# midicontrol_v5.net
KiCad netlist of a schematic drawn in EAGLE
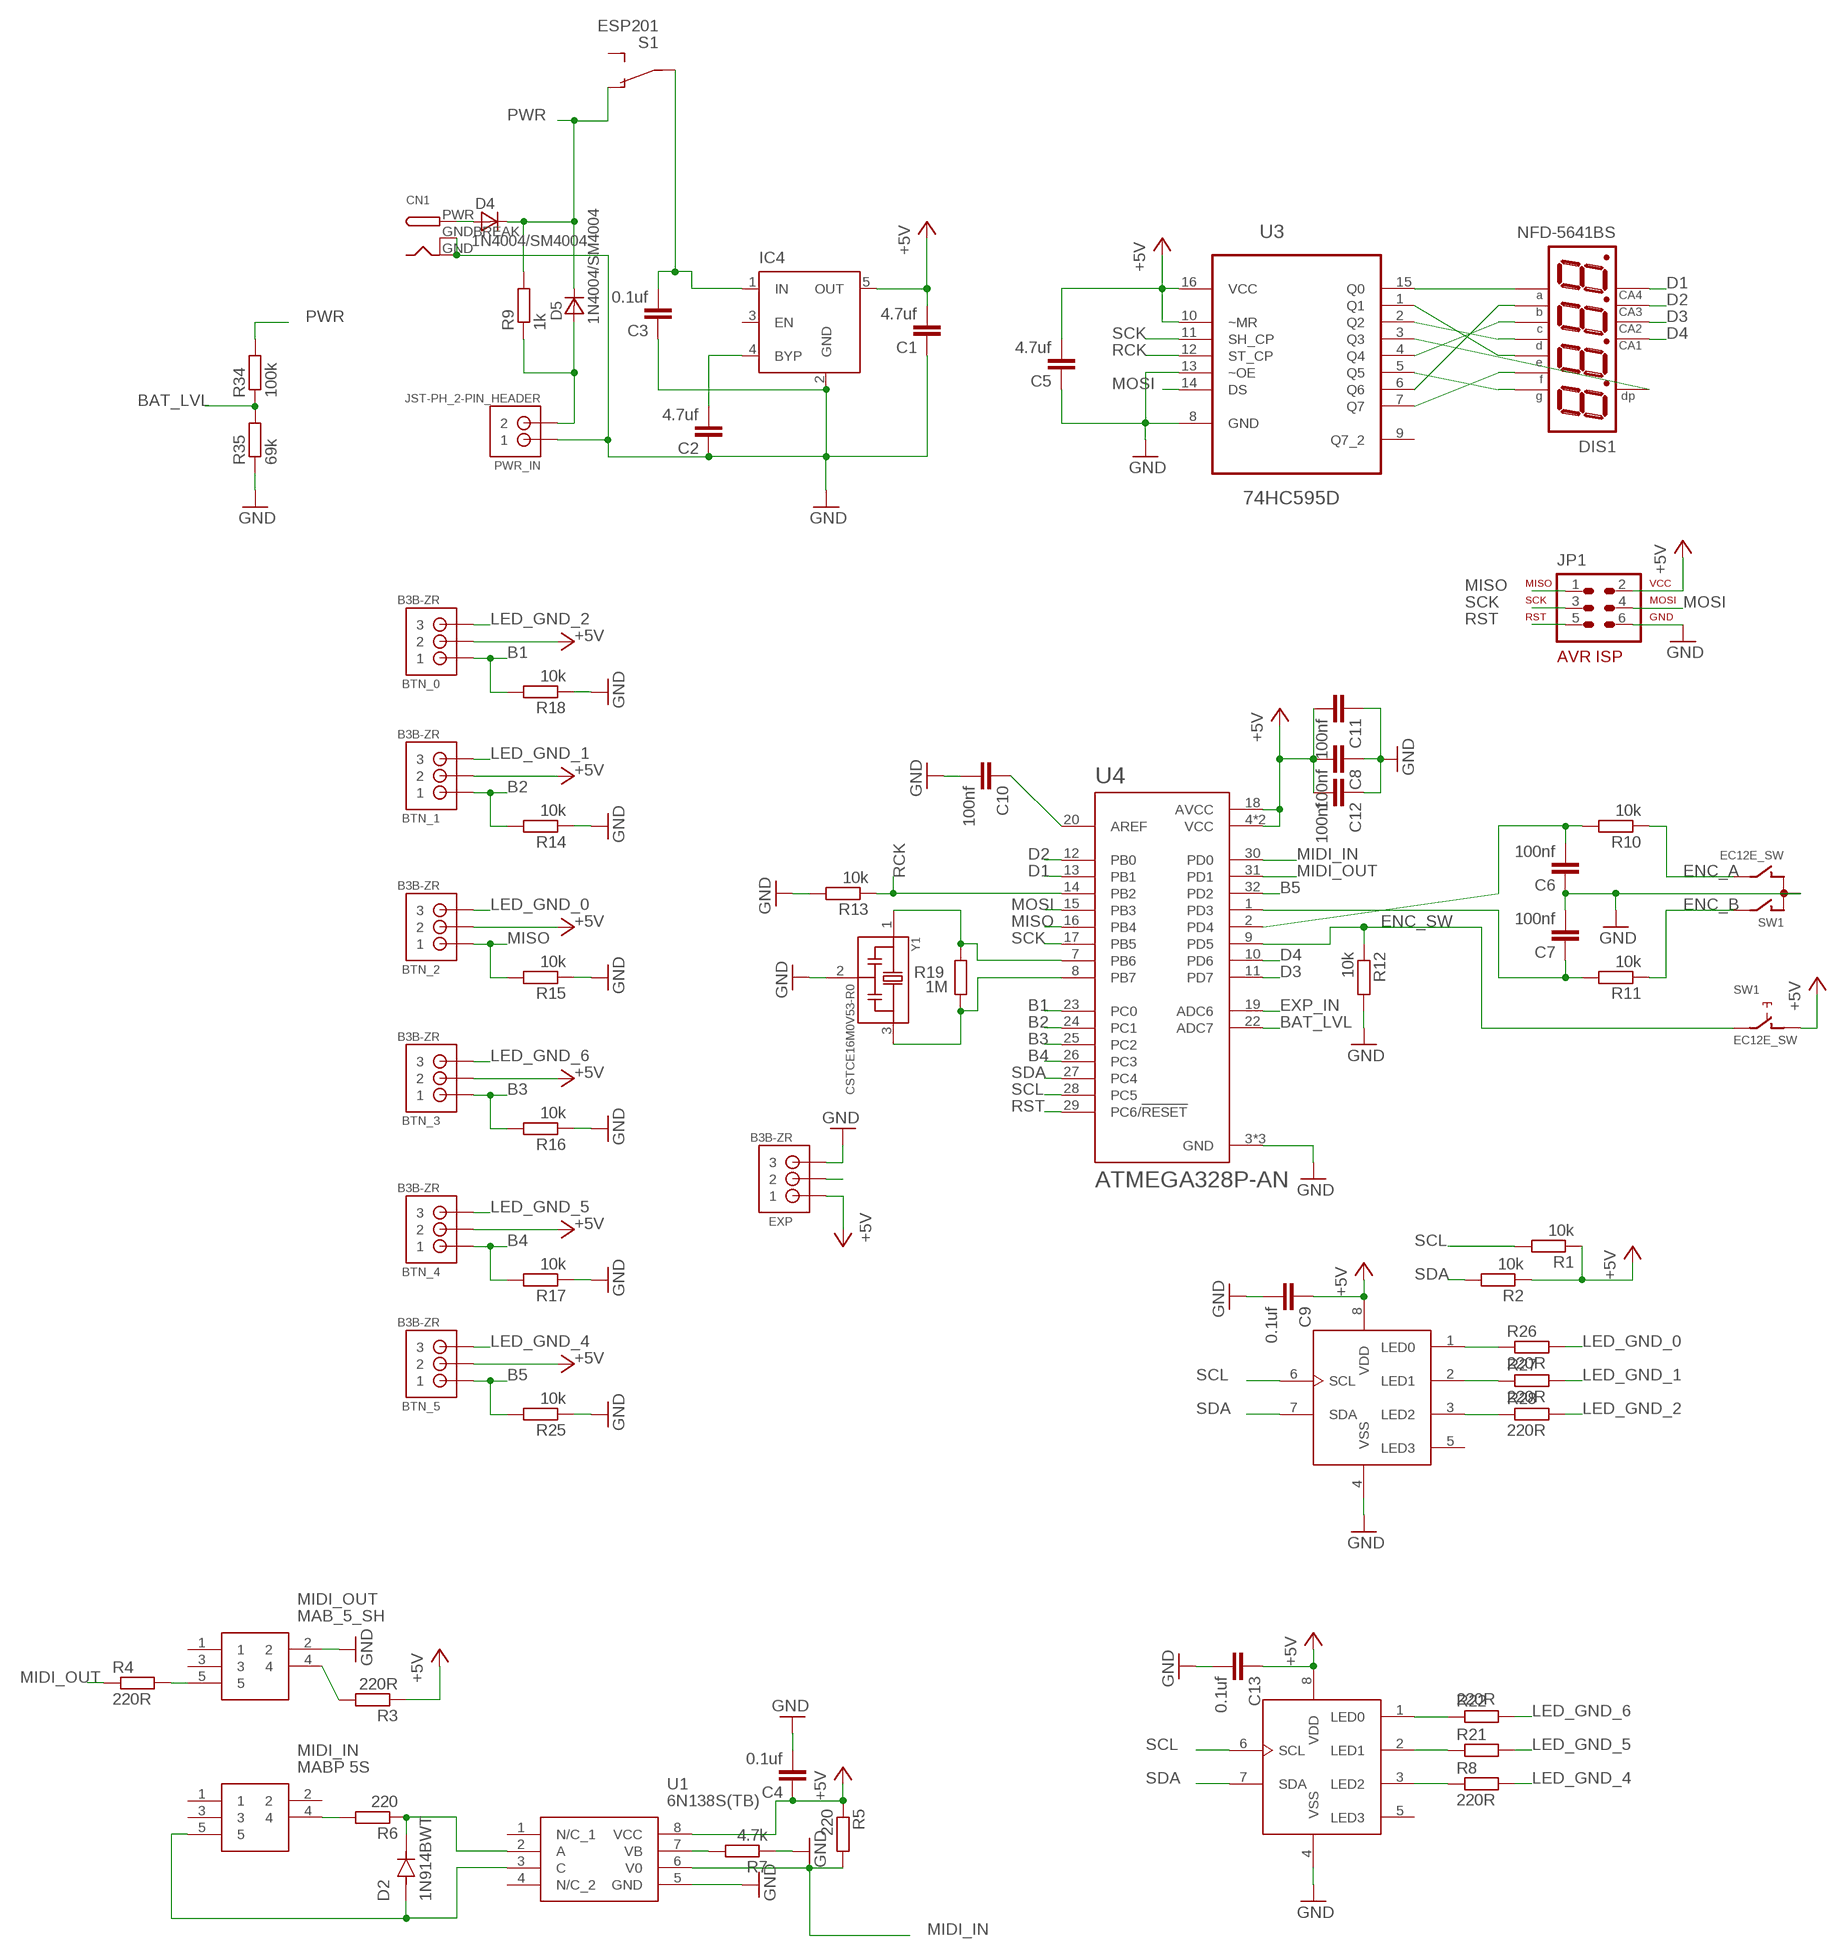
[diagram p0: schematic, sheet 1]

(export (version "E")
  (design (tool "Eeschema 10.0.6"))
  (components
    (comp (ref "BTN_0")
      (value "B3B-ZR")
      (footprint "eagle-import:B3B-ZR")
      (libsource (lib "eagle-import") (part "B3B-ZR"))
    )
    (comp (ref "BTN_1")
      (value "B3B-ZR")
      (footprint "eagle-import:B3B-ZR")
      (libsource (lib "eagle-import") (part "B3B-ZR"))
    )
    (comp (ref "BTN_2")
      (value "B3B-ZR")
      (footprint "eagle-import:B3B-ZR")
      (libsource (lib "eagle-import") (part "B3B-ZR"))
    )
    (comp (ref "BTN_3")
      (value "B3B-ZR")
      (footprint "eagle-import:B3B-ZR")
      (libsource (lib "eagle-import") (part "B3B-ZR"))
    )
    (comp (ref "BTN_4")
      (value "B3B-ZR")
      (footprint "eagle-import:B3B-ZR")
      (libsource (lib "eagle-import") (part "B3B-ZR"))
    )
    (comp (ref "BTN_5")
      (value "B3B-ZR")
      (footprint "eagle-import:B3B-ZR")
      (libsource (lib "eagle-import") (part "B3B-ZR"))
    )
    (comp (ref "C1")
      (value "4.7uf")
      (footprint "eagle-import:C1206")
      (libsource (lib "eagle-import") (part "C-EUC1206"))
    )
    (comp (ref "C2")
      (value "4.7uf")
      (footprint "eagle-import:C1206")
      (libsource (lib "eagle-import") (part "C-EUC1206"))
    )
    (comp (ref "C3")
      (value "0.1uf")
      (footprint "eagle-import:C1206")
      (libsource (lib "eagle-import") (part "C-EUC1206"))
    )
    (comp (ref "C4")
      (value "0.1uf")
      (footprint "eagle-import:C0603")
      (libsource (lib "eagle-import") (part "C-EUC0603"))
    )
    (comp (ref "C5")
      (value "4.7uf")
      (footprint "eagle-import:C0603")
      (libsource (lib "eagle-import") (part "C-EUC0603"))
    )
    (comp (ref "C6")
      (value "100nf")
      (footprint "eagle-import:C0603")
      (libsource (lib "eagle-import") (part "C-EUC0603"))
    )
    (comp (ref "C7")
      (value "100nf")
      (footprint "eagle-import:C0603")
      (libsource (lib "eagle-import") (part "C-EUC0603"))
    )
    (comp (ref "C8")
      (value "100nf")
      (footprint "eagle-import:C1206")
      (libsource (lib "eagle-import") (part "C-EUC1206"))
    )
    (comp (ref "C9")
      (value "0.1uf")
      (footprint "eagle-import:C0603")
      (libsource (lib "eagle-import") (part "C-EUC0603"))
    )
    (comp (ref "C10")
      (value "100nf")
      (footprint "eagle-import:C0603")
      (libsource (lib "eagle-import") (part "C-EUC0603"))
    )
    (comp (ref "C11")
      (value "100nf")
      (footprint "eagle-import:C0603")
      (libsource (lib "eagle-import") (part "C-EUC0603"))
    )
    (comp (ref "C12")
      (value "100nf")
      (footprint "eagle-import:C0603")
      (libsource (lib "eagle-import") (part "C-EUC0603"))
    )
    (comp (ref "C13")
      (value "0.1uf")
      (footprint "eagle-import:C0603")
      (libsource (lib "eagle-import") (part "C-EUC0603"))
    )
    (comp (ref "CN1")
      (value "DCBARRELPTH")
      (footprint "eagle-import:DCJACK_2MM_PTH")
      (libsource (lib "eagle-import") (part "DCBARRELPTH"))
    )
    (comp (ref "D2")
      (value "1N914BWT")
      (footprint "eagle-import:SODFL1608X70N")
      (fields (field (name "MF") "ON Semiconductor"))
      (libsource (lib "eagle-import") (part "1N914BWT"))
    )
    (comp (ref "D4")
      (value "1N4004/SM4004")
      (footprint "eagle-import:MELF-MLL41")
      (libsource (lib "eagle-import") (part "SM4004"))
    )
    (comp (ref "D5")
      (value "1N4004/SM4004")
      (footprint "eagle-import:MELF-MLL41")
      (libsource (lib "eagle-import") (part "SM4004"))
    )
    (comp (ref "DIS1")
      (value "NFD-5641BS")
      (footprint "eagle-import:NFD-5641")
      (libsource (lib "eagle-import") (part "NFD-5641BS"))
    )
    (comp (ref "EXP")
      (value "B3B-ZR")
      (footprint "eagle-import:B3B-ZR")
      (libsource (lib "eagle-import") (part "B3B-ZR"))
    )
    (comp (ref "IC4")
      (value "MIC5219XX")
      (footprint "eagle-import:SOT23-5")
      (libsource (lib "eagle-import") (part "MIC5219XX"))
    )
    (comp (ref "JP1")
      (value "AVR-ISP-6HORZ")
      (footprint "eagle-import:AVR-ISP-6R")
      (libsource (lib "eagle-import") (part "AVR-ISP-6HORZ"))
    )
    (comp (ref "MIDI_IN")
      (value "MABP 5S")
      (footprint "eagle-import:MAB-5-SH")
      (fields (field (name "MANUFACTURER_PART_NUMBER") "MAB 5 SH"))
      (libsource (lib "eagle-import") (part "MAB_5_SH"))
    )
    (comp (ref "MIDI_OUT")
      (value "MAB_5_SH")
      (footprint "eagle-import:MAB-5-SH")
      (fields (field (name "MANUFACTURER_PART_NUMBER") "MAB 5 SH"))
      (libsource (lib "eagle-import") (part "MAB_5_SH"))
    )
    (comp (ref "PCA1")
      (value "PCA9533")
      (footprint "eagle-import:SOIC8")
      (libsource (lib "eagle-import") (part "PCA9533"))
    )
    (comp (ref "PCA9533")
      (value "PCA9533")
      (footprint "eagle-import:SOIC8")
      (libsource (lib "eagle-import") (part "PCA9533"))
    )
    (comp (ref "PWR_IN")
      (value "JST-PH_2-PIN_HEADER")
      (footprint "eagle-import:JST_B2B-PH_HEADER")
      (libsource (lib "eagle-import") (part "JST-PH_2-PIN_HEADER"))
    )
    (comp (ref "R1")
      (value "10k")
      (footprint "eagle-import:R0603")
      (libsource (lib "eagle-import") (part "rcl_334_R-EU_R0603"))
    )
    (comp (ref "R2")
      (value "10k")
      (footprint "eagle-import:R0603")
      (libsource (lib "eagle-import") (part "rcl_334_R-EU_R0603"))
    )
    (comp (ref "R3")
      (value "220R")
      (footprint "eagle-import:R0603")
      (libsource (lib "eagle-import") (part "rcl_334_R-EU_R0603"))
    )
    (comp (ref "R4")
      (value "220R")
      (footprint "eagle-import:R0603")
      (libsource (lib "eagle-import") (part "rcl_334_R-EU_R0603"))
    )
    (comp (ref "R5")
      (value "220")
      (footprint "eagle-import:R0603")
      (libsource (lib "eagle-import") (part "rcl_334_R-EU_R0603"))
    )
    (comp (ref "R6")
      (value "220")
      (footprint "eagle-import:R0603")
      (libsource (lib "eagle-import") (part "rcl_334_R-EU_R0603"))
    )
    (comp (ref "R7")
      (value "4.7k")
      (footprint "eagle-import:R0603")
      (libsource (lib "eagle-import") (part "rcl_334_R-EU_R0603"))
    )
    (comp (ref "R8")
      (value "220R")
      (footprint "eagle-import:R0603")
      (libsource (lib "eagle-import") (part "rcl_334_R-EU_R0603"))
    )
    (comp (ref "R9")
      (value "1k")
      (footprint "eagle-import:R0603")
      (libsource (lib "eagle-import") (part "rcl_334_R-EU_R0603"))
    )
    (comp (ref "R10")
      (value "10k")
      (footprint "eagle-import:R0603")
      (libsource (lib "eagle-import") (part "rcl_334_R-EU_R0603"))
    )
    (comp (ref "R11")
      (value "10k")
      (footprint "eagle-import:R0603")
      (libsource (lib "eagle-import") (part "rcl_334_R-EU_R0603"))
    )
    (comp (ref "R12")
      (value "10k")
      (footprint "eagle-import:R0603")
      (libsource (lib "eagle-import") (part "rcl_334_R-EU_R0603"))
    )
    (comp (ref "R13")
      (value "10k")
      (footprint "eagle-import:R0603")
      (libsource (lib "eagle-import") (part "rcl_334_R-EU_R0603"))
    )
    (comp (ref "R14")
      (value "10k")
      (footprint "eagle-import:R0603")
      (libsource (lib "eagle-import") (part "rcl_334_R-EU_R0603"))
    )
    (comp (ref "R15")
      (value "10k")
      (footprint "eagle-import:R0603")
      (libsource (lib "eagle-import") (part "rcl_334_R-EU_R0603"))
    )
    (comp (ref "R16")
      (value "10k")
      (footprint "eagle-import:R0603")
      (libsource (lib "eagle-import") (part "rcl_334_R-EU_R0603"))
    )
    (comp (ref "R17")
      (value "10k")
      (footprint "eagle-import:R0603")
      (libsource (lib "eagle-import") (part "rcl_334_R-EU_R0603"))
    )
    (comp (ref "R18")
      (value "10k")
      (footprint "eagle-import:R0603")
      (libsource (lib "eagle-import") (part "rcl_334_R-EU_R0603"))
    )
    (comp (ref "R19")
      (value "1M")
      (footprint "eagle-import:R0603-ROUND")
      (libsource (lib "eagle-import") (part "R-EU_R0603"))
    )
    (comp (ref "R21")
      (value "220R")
      (footprint "eagle-import:R0603")
      (libsource (lib "eagle-import") (part "rcl_334_R-EU_R0603"))
    )
    (comp (ref "R22")
      (value "220R")
      (footprint "eagle-import:R0603")
      (libsource (lib "eagle-import") (part "rcl_334_R-EU_R0603"))
    )
    (comp (ref "R25")
      (value "10k")
      (footprint "eagle-import:R0603")
      (libsource (lib "eagle-import") (part "rcl_334_R-EU_R0603"))
    )
    (comp (ref "R26")
      (value "220R")
      (footprint "eagle-import:R0603")
      (libsource (lib "eagle-import") (part "rcl_334_R-EU_R0603"))
    )
    (comp (ref "R27")
      (value "220R")
      (footprint "eagle-import:R0603")
      (libsource (lib "eagle-import") (part "rcl_334_R-EU_R0603"))
    )
    (comp (ref "R28")
      (value "220R")
      (footprint "eagle-import:R0603")
      (libsource (lib "eagle-import") (part "rcl_334_R-EU_R0603"))
    )
    (comp (ref "R34")
      (value "100k")
      (footprint "eagle-import:R0603")
      (libsource (lib "eagle-import") (part "rcl_334_R-EU_R0603"))
    )
    (comp (ref "R35")
      (value "69k")
      (footprint "eagle-import:R0603")
      (libsource (lib "eagle-import") (part "rcl_334_R-EU_R0603"))
    )
    (comp (ref "S1")
      (value "ESP201")
      (footprint "eagle-import:ESP201")
      (libsource (lib "eagle-import") (part "ESP201"))
    )
    (comp (ref "SW1")
      (value "EC12E_SW")
      (footprint "eagle-import:ALPS_EC12E_SW")
      (fields (field (name "MPN") "EC12E2424407"))
      (libsource (lib "eagle-import") (part "EC12E_SW"))
    )
    (comp (ref "U1")
      (value "6N138S(TB)")
      (footprint "eagle-import:SOP254P1030X460-8N")
      (fields (field (name "MOUSER_PART_NUMBER") "638-6N138STB"))
      (libsource (lib "eagle-import") (part "6N138S(TB)"))
    )
    (comp (ref "U3")
      (value "74HC595D")
      (footprint "eagle-import:SOIC127P600X175-16N")
      (fields (field (name "MF") "Toshiba Semiconductor"))
      (libsource (lib "eagle-import") (part "74HC595D"))
    )
    (comp (ref "U4")
      (value "ATMEGA328P-AN")
      (footprint "eagle-import:QFP80P900X900X120-32N")
      (fields (field (name "MF") "Microchip"))
      (libsource (lib "eagle-import") (part "ATMEGA328P-AN"))
    )
    (comp (ref "Y1")
      (value "CSTCE16M0V53-R0")
      (footprint "eagle-import:OSC_CSTCE16M0V53-R0")
      (fields (field (name "MF") "Murata"))
      (libsource (lib "eagle-import") (part "CSTCE16M0V53-R0"))
    )
  )
  (nets
    (net (code "1") (name "+5V") (class "Default")
      (node (ref "BTN_0") (pin "2") (pinfunction "2_2") (pintype "bidirectional"))
      (node (ref "BTN_1") (pin "2") (pinfunction "2_2") (pintype "bidirectional"))
      (node (ref "BTN_2") (pin "2") (pinfunction "2_2") (pintype "bidirectional"))
      (node (ref "BTN_3") (pin "2") (pinfunction "2_2") (pintype "bidirectional"))
      (node (ref "BTN_4") (pin "2") (pinfunction "2_2") (pintype "bidirectional"))
      (node (ref "BTN_5") (pin "2") (pinfunction "2_2") (pintype "bidirectional"))
      (node (ref "C1") (pin "2") (pinfunction "2_2") (pintype "passive"))
      (node (ref "C11") (pin "2") (pinfunction "2_2") (pintype "passive"))
      (node (ref "C12") (pin "2") (pinfunction "2_2") (pintype "passive"))
      (node (ref "C13") (pin "1") (pinfunction "1_1") (pintype "passive"))
      (node (ref "C4") (pin "1") (pinfunction "1_1") (pintype "passive"))
      (node (ref "C5") (pin "2") (pinfunction "2_2") (pintype "passive"))
      (node (ref "C8") (pin "2") (pinfunction "2_2") (pintype "passive"))
      (node (ref "C9") (pin "1") (pinfunction "1_1") (pintype "passive"))
      (node (ref "EXP") (pin "1") (pinfunction "1_1") (pintype "bidirectional"))
      (node (ref "IC4") (pin "5") (pinfunction "OUT_5") (pintype "output"))
      (node (ref "JP1") (pin "2") (pinfunction "2_2") (pintype "passive"))
      (node (ref "PCA1") (pin "8") (pinfunction "VDD_8") (pintype "power_in"))
      (node (ref "PCA9533") (pin "8") (pinfunction "VDD_8") (pintype "power_in"))
      (node (ref "R1") (pin "1") (pinfunction "1_1") (pintype "passive"))
      (node (ref "R2") (pin "1") (pinfunction "1_1") (pintype "passive"))
      (node (ref "R3") (pin "1") (pinfunction "1_1") (pintype "passive"))
      (node (ref "R5") (pin "1") (pinfunction "1_1") (pintype "passive"))
      (node (ref "SW1") (pin "D") (pinfunction "1_D") (pintype "passive"))
      (node (ref "U1") (pin "8") (pinfunction "VCC_8") (pintype "power_in"))
      (node (ref "U3") (pin "10") (pinfunction "~{MR}_10") (pintype "passive"))
      (node (ref "U3") (pin "16") (pinfunction "VCC_16") (pintype "power_in"))
      (node (ref "U4") (pin "18") (pinfunction "AVCC_18") (pintype "power_in"))
      (node (ref "U4") (pin "4") (pinfunction "VCC_4") (pintype "power_in"))
      (node (ref "U4") (pin "6") (pinfunction "VCC_6") (pintype "power_in"))
    )
    (net (code "2") (name "/B1") (class "Default")
      (node (ref "BTN_0") (pin "1") (pinfunction "1_1") (pintype "bidirectional"))
      (node (ref "R18") (pin "2") (pinfunction "2_2") (pintype "passive"))
      (node (ref "U4") (pin "23") (pinfunction "PC0_23") (pintype "bidirectional"))
    )
    (net (code "3") (name "/B2") (class "Default")
      (node (ref "BTN_1") (pin "1") (pinfunction "1_1") (pintype "bidirectional"))
      (node (ref "R14") (pin "2") (pinfunction "2_2") (pintype "passive"))
      (node (ref "U4") (pin "24") (pinfunction "PC1_24") (pintype "bidirectional"))
    )
    (net (code "4") (name "/B3") (class "Default")
      (node (ref "BTN_3") (pin "1") (pinfunction "1_1") (pintype "bidirectional"))
      (node (ref "R16") (pin "2") (pinfunction "2_2") (pintype "passive"))
      (node (ref "U4") (pin "25") (pinfunction "PC2_25") (pintype "bidirectional"))
    )
    (net (code "5") (name "/B4") (class "Default")
      (node (ref "BTN_4") (pin "1") (pinfunction "1_1") (pintype "bidirectional"))
      (node (ref "R17") (pin "2") (pinfunction "2_2") (pintype "passive"))
      (node (ref "U4") (pin "26") (pinfunction "PC3_26") (pintype "bidirectional"))
    )
    (net (code "6") (name "/B5") (class "Default")
      (node (ref "BTN_5") (pin "1") (pinfunction "1_1") (pintype "bidirectional"))
      (node (ref "R25") (pin "2") (pinfunction "2_2") (pintype "passive"))
      (node (ref "U4") (pin "32") (pinfunction "PD2_32") (pintype "bidirectional"))
    )
    (net (code "7") (name "/BAT_LVL") (class "Default")
      (node (ref "R34") (pin "1") (pinfunction "1_1") (pintype "passive"))
      (node (ref "R35") (pin "2") (pinfunction "2_2") (pintype "passive"))
      (node (ref "U4") (pin "22") (pinfunction "ADC7_22") (pintype "bidirectional"))
    )
    (net (code "8") (name "/D1") (class "Default")
      (node (ref "DIS1") (pin "P$6") (pinfunction "P$6_P$6") (pintype "bidirectional"))
      (node (ref "U4") (pin "13") (pinfunction "PB1_13") (pintype "bidirectional"))
    )
    (net (code "9") (name "/D2") (class "Default")
      (node (ref "DIS1") (pin "P$8") (pinfunction "P$8_P$8") (pintype "bidirectional"))
      (node (ref "U4") (pin "12") (pinfunction "PB0_12") (pintype "bidirectional"))
    )
    (net (code "10") (name "/D3") (class "Default")
      (node (ref "DIS1") (pin "P$9") (pinfunction "P$9_P$9") (pintype "bidirectional"))
      (node (ref "U4") (pin "11") (pinfunction "PD7_11") (pintype "bidirectional"))
    )
    (net (code "11") (name "/D4") (class "Default")
      (node (ref "DIS1") (pin "P$12") (pinfunction "P$12_P$12") (pintype "bidirectional"))
      (node (ref "U4") (pin "10") (pinfunction "PD6_10") (pintype "bidirectional"))
    )
    (net (code "12") (name "/ENC_A") (class "Default")
      (node (ref "R10") (pin "1") (pinfunction "1_1") (pintype "passive"))
      (node (ref "SW1") (pin "B") (pinfunction "B_B") (pintype "passive"))
    )
    (net (code "13") (name "/ENC_B") (class "Default")
      (node (ref "R11") (pin "1") (pinfunction "1_1") (pintype "passive"))
      (node (ref "SW1") (pin "A") (pinfunction "A_A") (pintype "passive"))
    )
    (net (code "14") (name "/ENC_SW") (class "Default")
      (node (ref "R12") (pin "1") (pinfunction "1_1") (pintype "passive"))
      (node (ref "SW1") (pin "E") (pinfunction "2_E") (pintype "passive"))
      (node (ref "U4") (pin "9") (pinfunction "PD5_9") (pintype "bidirectional"))
    )
    (net (code "15") (name "/EXP_IN") (class "Default")
      (node (ref "EXP") (pin "2") (pinfunction "2_2") (pintype "bidirectional"))
      (node (ref "U4") (pin "19") (pinfunction "ADC6_19") (pintype "bidirectional"))
    )
    (net (code "16") (name "/LED_GND_0") (class "Default")
      (node (ref "BTN_2") (pin "3") (pinfunction "3_3") (pintype "bidirectional"))
      (node (ref "R26") (pin "2") (pinfunction "2_2") (pintype "passive"))
    )
    (net (code "17") (name "/LED_GND_1") (class "Default")
      (node (ref "BTN_1") (pin "3") (pinfunction "3_3") (pintype "bidirectional"))
      (node (ref "R27") (pin "2") (pinfunction "2_2") (pintype "passive"))
    )
    (net (code "18") (name "/LED_GND_2") (class "Default")
      (node (ref "BTN_0") (pin "3") (pinfunction "3_3") (pintype "bidirectional"))
      (node (ref "R28") (pin "2") (pinfunction "2_2") (pintype "passive"))
    )
    (net (code "19") (name "/LED_GND_4") (class "Default")
      (node (ref "BTN_5") (pin "3") (pinfunction "3_3") (pintype "bidirectional"))
      (node (ref "R8") (pin "2") (pinfunction "2_2") (pintype "passive"))
    )
    (net (code "20") (name "/LED_GND_5") (class "Default")
      (node (ref "BTN_4") (pin "3") (pinfunction "3_3") (pintype "bidirectional"))
      (node (ref "R21") (pin "2") (pinfunction "2_2") (pintype "passive"))
    )
    (net (code "21") (name "/LED_GND_6") (class "Default")
      (node (ref "BTN_3") (pin "3") (pinfunction "3_3") (pintype "bidirectional"))
      (node (ref "R22") (pin "2") (pinfunction "2_2") (pintype "passive"))
    )
    (net (code "22") (name "/MIDI_IN") (class "Default")
      (node (ref "R5") (pin "2") (pinfunction "2_2") (pintype "passive"))
      (node (ref "U1") (pin "6") (pinfunction "V0_6") (pintype "bidirectional"))
      (node (ref "U4") (pin "30") (pinfunction "PD0_30") (pintype "bidirectional"))
    )
    (net (code "23") (name "/MIDI_OUT") (class "Default")
      (node (ref "R4") (pin "1") (pinfunction "1_1") (pintype "passive"))
      (node (ref "U4") (pin "31") (pinfunction "PD1_31") (pintype "bidirectional"))
    )
    (net (code "24") (name "/MISO") (class "Default")
      (node (ref "BTN_2") (pin "1") (pinfunction "1_1") (pintype "bidirectional"))
      (node (ref "JP1") (pin "1") (pinfunction "1_1") (pintype "passive"))
      (node (ref "R15") (pin "2") (pinfunction "2_2") (pintype "passive"))
      (node (ref "U4") (pin "16") (pinfunction "PB4_16") (pintype "bidirectional"))
    )
    (net (code "25") (name "/MOSI") (class "Default")
      (node (ref "JP1") (pin "4") (pinfunction "4_4") (pintype "passive"))
      (node (ref "U3") (pin "14") (pinfunction "DS_14") (pintype "input"))
      (node (ref "U4") (pin "15") (pinfunction "PB3_15") (pintype "bidirectional"))
    )
    (net (code "26") (name "/PWR") (class "Default")
      (node (ref "D4") (pin "C") (pinfunction "C_C") (pintype "passive"))
      (node (ref "D5") (pin "C") (pinfunction "C_C") (pintype "passive"))
      (node (ref "R34") (pin "2") (pinfunction "2_2") (pintype "passive"))
      (node (ref "R9") (pin "2") (pinfunction "2_2") (pintype "passive"))
      (node (ref "S1") (pin "P$3") (pinfunction "O_P$3") (pintype "passive"))
    )
    (net (code "27") (name "/RCK") (class "Default")
      (node (ref "R13") (pin "1") (pinfunction "1_1") (pintype "passive"))
      (node (ref "U3") (pin "12") (pinfunction "ST_CP_12") (pintype "passive"))
      (node (ref "U4") (pin "14") (pinfunction "PB2_14") (pintype "bidirectional"))
    )
    (net (code "28") (name "/RST") (class "Default")
      (node (ref "JP1") (pin "5") (pinfunction "5_5") (pintype "passive"))
      (node (ref "U4") (pin "29") (pinfunction "PC6/~{RESET}_29") (pintype "bidirectional"))
    )
    (net (code "29") (name "/SCK") (class "Default")
      (node (ref "JP1") (pin "3") (pinfunction "3_3") (pintype "passive"))
      (node (ref "U3") (pin "11") (pinfunction "SH_CP_11") (pintype "passive"))
      (node (ref "U4") (pin "17") (pinfunction "PB5_17") (pintype "bidirectional"))
    )
    (net (code "30") (name "/SCL") (class "Default")
      (node (ref "PCA1") (pin "6") (pinfunction "SCL_6") (pintype "input"))
      (node (ref "PCA9533") (pin "6") (pinfunction "SCL_6") (pintype "input"))
      (node (ref "R1") (pin "2") (pinfunction "2_2") (pintype "passive"))
      (node (ref "U4") (pin "28") (pinfunction "PC5_28") (pintype "bidirectional"))
    )
    (net (code "31") (name "/SDA") (class "Default")
      (node (ref "PCA1") (pin "7") (pinfunction "SDA_7") (pintype "bidirectional"))
      (node (ref "PCA9533") (pin "7") (pinfunction "SDA_7") (pintype "bidirectional"))
      (node (ref "R2") (pin "2") (pinfunction "2_2") (pintype "passive"))
      (node (ref "U4") (pin "27") (pinfunction "PC4_27") (pintype "bidirectional"))
    )
    (net (code "32") (name "GND") (class "Default")
      (node (ref "C1") (pin "1") (pinfunction "1_1") (pintype "passive"))
      (node (ref "C10") (pin "2") (pinfunction "2_2") (pintype "passive"))
      (node (ref "C11") (pin "1") (pinfunction "1_1") (pintype "passive"))
      (node (ref "C12") (pin "1") (pinfunction "1_1") (pintype "passive"))
      (node (ref "C13") (pin "2") (pinfunction "2_2") (pintype "passive"))
      (node (ref "C2") (pin "1") (pinfunction "1_1") (pintype "passive"))
      (node (ref "C3") (pin "1") (pinfunction "1_1") (pintype "passive"))
      (node (ref "C4") (pin "2") (pinfunction "2_2") (pintype "passive"))
      (node (ref "C5") (pin "1") (pinfunction "1_1") (pintype "passive"))
      (node (ref "C6") (pin "1") (pinfunction "1_1") (pintype "passive"))
      (node (ref "C7") (pin "2") (pinfunction "2_2") (pintype "passive"))
      (node (ref "C8") (pin "1") (pinfunction "1_1") (pintype "passive"))
      (node (ref "C9") (pin "2") (pinfunction "2_2") (pintype "passive"))
      (node (ref "CN1") (pin "GND") (pinfunction "GND_GND") (pintype "power_in"))
      (node (ref "CN1") (pin "GNDBREAK") (pinfunction "GNDBREAK_GNDBREAK") (pintype "power_in"))
      (node (ref "EXP") (pin "3") (pinfunction "3_3") (pintype "bidirectional"))
      (node (ref "IC4") (pin "2") (pinfunction "GND_2") (pintype "power_in"))
      (node (ref "JP1") (pin "6") (pinfunction "6_6") (pintype "passive"))
      (node (ref "MIDI_OUT") (pin "2") (pinfunction "2_2") (pintype "bidirectional"))
      (node (ref "PCA1") (pin "4") (pinfunction "VSS_4") (pintype "power_in"))
      (node (ref "PCA9533") (pin "4") (pinfunction "VSS_4") (pintype "power_in"))
      (node (ref "PWR_IN") (pin "P1") (pinfunction "1_P1") (pintype "bidirectional"))
      (node (ref "R12") (pin "2") (pinfunction "2_2") (pintype "passive"))
      (node (ref "R13") (pin "2") (pinfunction "2_2") (pintype "passive"))
      (node (ref "R14") (pin "1") (pinfunction "1_1") (pintype "passive"))
      (node (ref "R15") (pin "1") (pinfunction "1_1") (pintype "passive"))
      (node (ref "R16") (pin "1") (pinfunction "1_1") (pintype "passive"))
      (node (ref "R17") (pin "1") (pinfunction "1_1") (pintype "passive"))
      (node (ref "R18") (pin "1") (pinfunction "1_1") (pintype "passive"))
      (node (ref "R25") (pin "1") (pinfunction "1_1") (pintype "passive"))
      (node (ref "R35") (pin "1") (pinfunction "1_1") (pintype "passive"))
      (node (ref "R7") (pin "1") (pinfunction "1_1") (pintype "passive"))
      (node (ref "SW1") (pin "C") (pinfunction "C_C") (pintype "passive"))
      (node (ref "U1") (pin "5") (pinfunction "GND_5") (pintype "power_in"))
      (node (ref "U3") (pin "13") (pinfunction "~{OE}_13") (pintype "input"))
      (node (ref "U3") (pin "8") (pinfunction "GND_8") (pintype "passive"))
      (node (ref "U4") (pin "21") (pinfunction "GND_21") (pintype "power_in"))
      (node (ref "U4") (pin "3") (pinfunction "GND_3") (pintype "power_in"))
      (node (ref "U4") (pin "5") (pinfunction "GND_5") (pintype "power_in"))
      (node (ref "Y1") (pin "2") (pinfunction "2_2") (pintype "power_in"))
    )
    (net (code "33") (name "Net-(CN1-PadPWR)") (class "Default")
      (node (ref "CN1") (pin "PWR") (pinfunction "PWR_PWR") (pintype "power_in"))
      (node (ref "D4") (pin "A") (pinfunction "A_A") (pintype "passive"))
    )
    (net (code "34") (name "Net-(D2-K)") (class "Default")
      (node (ref "D2") (pin "C") (pinfunction "K_C") (pintype "passive"))
      (node (ref "R6") (pin "1") (pinfunction "1_1") (pintype "passive"))
      (node (ref "U1") (pin "2") (pinfunction "A_2") (pintype "bidirectional"))
    )
    (net (code "35") (name "Net-(IC4-BYP)") (class "Default")
      (node (ref "C2") (pin "2") (pinfunction "2_2") (pintype "passive"))
      (node (ref "IC4") (pin "4") (pinfunction "BYP_4") (pintype "passive"))
    )
    (net (code "36") (name "Net-(IC4-IN)") (class "Default")
      (node (ref "C3") (pin "2") (pinfunction "2_2") (pintype "passive"))
      (node (ref "IC4") (pin "1") (pinfunction "IN_1") (pintype "input"))
      (node (ref "S1") (pin "P$1") (pinfunction "P_P$1") (pintype "passive"))
    )
    (net (code "37") (name "Net-(MIDI_IN-Pad4)") (class "Default")
      (node (ref "MIDI_IN") (pin "4") (pinfunction "4_4") (pintype "bidirectional"))
      (node (ref "R6") (pin "2") (pinfunction "2_2") (pintype "passive"))
    )
    (net (code "38") (name "Net-(MIDI_OUT-Pad4)") (class "Default")
      (node (ref "MIDI_OUT") (pin "4") (pinfunction "4_4") (pintype "bidirectional"))
      (node (ref "R3") (pin "2") (pinfunction "2_2") (pintype "passive"))
    )
    (net (code "39") (name "Net-(MIDI_OUT-Pad5)") (class "Default")
      (node (ref "MIDI_OUT") (pin "5") (pinfunction "5_5") (pintype "bidirectional"))
      (node (ref "R4") (pin "2") (pinfunction "2_2") (pintype "passive"))
    )
    (net (code "40") (name "Net-(PCA1-LED0)") (class "Default")
      (node (ref "PCA1") (pin "1") (pinfunction "LED0_1") (pintype "bidirectional"))
      (node (ref "R22") (pin "1") (pinfunction "1_1") (pintype "passive"))
    )
    (net (code "41") (name "Net-(PCA1-LED1)") (class "Default")
      (node (ref "PCA1") (pin "2") (pinfunction "LED1_2") (pintype "bidirectional"))
      (node (ref "R21") (pin "1") (pinfunction "1_1") (pintype "passive"))
    )
    (net (code "42") (name "Net-(PCA1-LED2)") (class "Default")
      (node (ref "PCA1") (pin "3") (pinfunction "LED2_3") (pintype "bidirectional"))
      (node (ref "R8") (pin "1") (pinfunction "1_1") (pintype "passive"))
    )
    (net (code "43") (name "Net-(PCA9533-LED0)") (class "Default")
      (node (ref "PCA9533") (pin "1") (pinfunction "LED0_1") (pintype "bidirectional"))
      (node (ref "R26") (pin "1") (pinfunction "1_1") (pintype "passive"))
    )
    (net (code "44") (name "Net-(PCA9533-LED1)") (class "Default")
      (node (ref "PCA9533") (pin "2") (pinfunction "LED1_2") (pintype "bidirectional"))
      (node (ref "R27") (pin "1") (pinfunction "1_1") (pintype "passive"))
    )
    (net (code "45") (name "Net-(PCA9533-LED2)") (class "Default")
      (node (ref "PCA9533") (pin "3") (pinfunction "LED2_3") (pintype "bidirectional"))
      (node (ref "R28") (pin "1") (pinfunction "1_1") (pintype "passive"))
    )
    (net (code "46") (name "Net-(PWR_IN-2)") (class "Default")
      (node (ref "D5") (pin "A") (pinfunction "A_A") (pintype "passive"))
      (node (ref "PWR_IN") (pin "P2") (pinfunction "2_P2") (pintype "bidirectional"))
      (node (ref "R9") (pin "1") (pinfunction "1_1") (pintype "passive"))
    )
    (net (code "47") (name "Net-(U1-C)") (class "Default")
      (node (ref "D2") (pin "A") (pinfunction "A_A") (pintype "passive"))
      (node (ref "MIDI_IN") (pin "5") (pinfunction "5_5") (pintype "bidirectional"))
      (node (ref "U1") (pin "3") (pinfunction "C_3") (pintype "bidirectional"))
    )
    (net (code "48") (name "Net-(U1-VB)") (class "Default")
      (node (ref "R7") (pin "2") (pinfunction "2_2") (pintype "passive"))
      (node (ref "U1") (pin "7") (pinfunction "VB_7") (pintype "bidirectional"))
    )
    (net (code "49") (name "Net-(U3-Q0)") (class "Default")
      (node (ref "DIS1") (pin "P$11") (pinfunction "P$11_P$11") (pintype "bidirectional"))
      (node (ref "U3") (pin "15") (pinfunction "Q0_15") (pintype "output"))
    )
    (net (code "50") (name "Net-(U3-Q1)") (class "Default")
      (node (ref "DIS1") (pin "P$1") (pinfunction "P$1_P$1") (pintype "bidirectional"))
      (node (ref "U3") (pin "1") (pinfunction "Q1_1") (pintype "output"))
    )
    (net (code "51") (name "Net-(U3-Q2)") (class "Default")
      (node (ref "DIS1") (pin "P$2") (pinfunction "P$2_P$2") (pintype "bidirectional"))
      (node (ref "U3") (pin "2") (pinfunction "Q2_2") (pintype "output"))
    )
    (net (code "52") (name "Net-(U3-Q3)") (class "Default")
      (node (ref "DIS1") (pin "P$3") (pinfunction "P$3_P$3") (pintype "bidirectional"))
      (node (ref "U3") (pin "3") (pinfunction "Q3_3") (pintype "output"))
    )
    (net (code "53") (name "Net-(U3-Q4)") (class "Default")
      (node (ref "DIS1") (pin "P$4") (pinfunction "P$4_P$4") (pintype "bidirectional"))
      (node (ref "U3") (pin "4") (pinfunction "Q4_4") (pintype "output"))
    )
    (net (code "54") (name "Net-(U3-Q5)") (class "Default")
      (node (ref "DIS1") (pin "P$5") (pinfunction "P$5_P$5") (pintype "bidirectional"))
      (node (ref "U3") (pin "5") (pinfunction "Q5_5") (pintype "output"))
    )
    (net (code "55") (name "Net-(U3-Q6)") (class "Default")
      (node (ref "DIS1") (pin "P$7") (pinfunction "P$7_P$7") (pintype "bidirectional"))
      (node (ref "U3") (pin "6") (pinfunction "Q6_6") (pintype "output"))
    )
    (net (code "56") (name "Net-(U3-Q7)") (class "Default")
      (node (ref "DIS1") (pin "P$10") (pinfunction "P$10_P$10") (pintype "bidirectional"))
      (node (ref "U3") (pin "7") (pinfunction "Q7_7") (pintype "output"))
    )
    (net (code "57") (name "Net-(U4-AREF)") (class "Default")
      (node (ref "C10") (pin "1") (pinfunction "1_1") (pintype "passive"))
      (node (ref "U4") (pin "20") (pinfunction "AREF_20") (pintype "input"))
    )
    (net (code "58") (name "Net-(U4-PB6)") (class "Default")
      (node (ref "R19") (pin "2") (pinfunction "2_2") (pintype "passive"))
      (node (ref "U4") (pin "7") (pinfunction "PB6_7") (pintype "bidirectional"))
      (node (ref "Y1") (pin "1") (pinfunction "1_1") (pintype "passive"))
    )
    (net (code "59") (name "Net-(U4-PB7)") (class "Default")
      (node (ref "R19") (pin "1") (pinfunction "1_1") (pintype "passive"))
      (node (ref "U4") (pin "8") (pinfunction "PB7_8") (pintype "bidirectional"))
      (node (ref "Y1") (pin "3") (pinfunction "3_3") (pintype "passive"))
    )
    (net (code "60") (name "Net-(U4-PD3)") (class "Default")
      (node (ref "C7") (pin "1") (pinfunction "1_1") (pintype "passive"))
      (node (ref "R11") (pin "2") (pinfunction "2_2") (pintype "passive"))
      (node (ref "U4") (pin "1") (pinfunction "PD3_1") (pintype "bidirectional"))
    )
    (net (code "61") (name "Net-(U4-PD4)") (class "Default")
      (node (ref "C6") (pin "2") (pinfunction "2_2") (pintype "passive"))
      (node (ref "R10") (pin "2") (pinfunction "2_2") (pintype "passive"))
      (node (ref "U4") (pin "2") (pinfunction "PD4_2") (pintype "bidirectional"))
    )
    (net (code "62") (name "unconnected-(IC4-EN-Pad3)") (class "Default")
      (node (ref "IC4") (pin "3") (pinfunction "EN_3") (pintype "input"))
    )
    (net (code "63") (name "unconnected-(MIDI_IN-Pad1)") (class "Default")
      (node (ref "MIDI_IN") (pin "1") (pinfunction "1_1") (pintype "bidirectional"))
    )
    (net (code "64") (name "unconnected-(MIDI_IN-Pad2)") (class "Default")
      (node (ref "MIDI_IN") (pin "2") (pinfunction "2_2") (pintype "bidirectional"))
    )
    (net (code "65") (name "unconnected-(MIDI_IN-Pad3)") (class "Default")
      (node (ref "MIDI_IN") (pin "3") (pinfunction "3_3") (pintype "bidirectional"))
    )
    (net (code "66") (name "unconnected-(MIDI_OUT-Pad1)") (class "Default")
      (node (ref "MIDI_OUT") (pin "1") (pinfunction "1_1") (pintype "bidirectional"))
    )
    (net (code "67") (name "unconnected-(MIDI_OUT-Pad3)") (class "Default")
      (node (ref "MIDI_OUT") (pin "3") (pinfunction "3_3") (pintype "bidirectional"))
    )
    (net (code "68") (name "unconnected-(PCA1-LED3-Pad5)") (class "Default")
      (node (ref "PCA1") (pin "5") (pinfunction "LED3_5") (pintype "bidirectional"))
    )
    (net (code "69") (name "unconnected-(PCA9533-LED3-Pad5)") (class "Default")
      (node (ref "PCA9533") (pin "5") (pinfunction "LED3_5") (pintype "bidirectional"))
    )
    (net (code "70") (name "unconnected-(S1-S-PadP$2)") (class "Default")
      (node (ref "S1") (pin "P$2") (pinfunction "S_P$2") (pintype "passive"))
    )
    (net (code "71") (name "unconnected-(U1-N{slash}C_1-Pad1)") (class "Default")
      (node (ref "U1") (pin "1") (pinfunction "N/C_1_1") (pintype "bidirectional"))
    )
    (net (code "72") (name "unconnected-(U1-N{slash}C_2-Pad4)") (class "Default")
      (node (ref "U1") (pin "4") (pinfunction "N/C_2_4") (pintype "bidirectional"))
    )
    (net (code "73") (name "unconnected-(U3-Q7_2-Pad9)") (class "Default")
      (node (ref "U3") (pin "9") (pinfunction "Q7_2_9") (pintype "output"))
    )
  )
)
